# Breakout_v4.net
KiCad netlist of a schematic drawn in Altium Designer
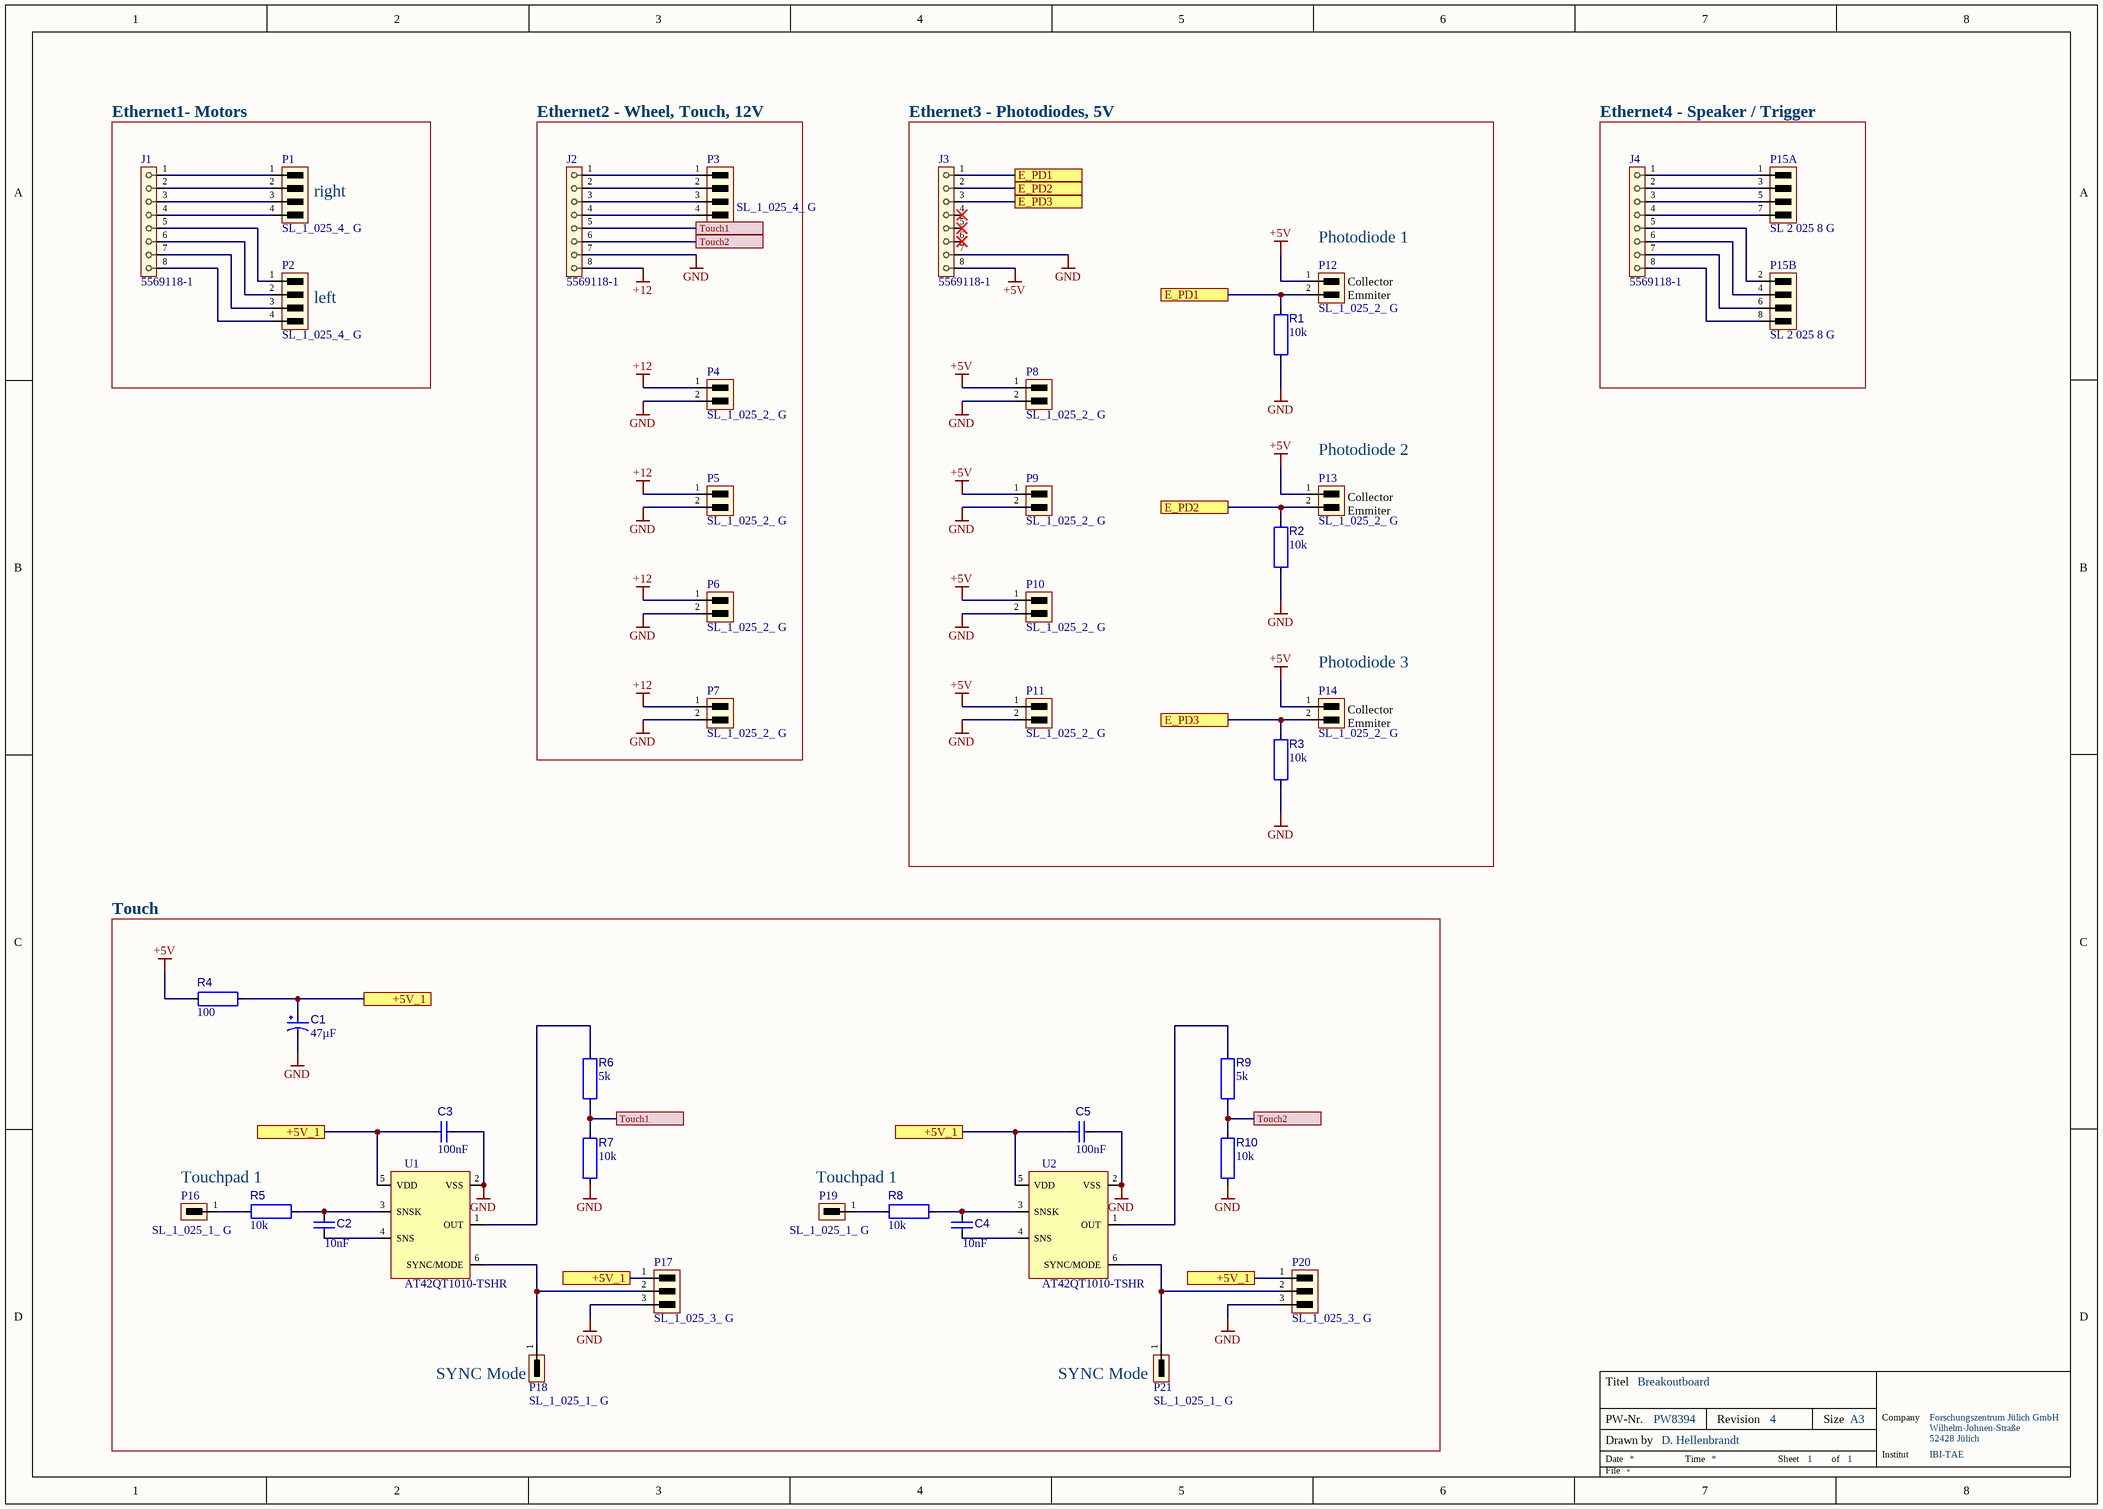
[diagram p0: Breakout_v4.SchDoc]

(export (version "E")
  (design (tool "Eeschema 10.0.6"))
  (components
    (comp (ref "C1")
      (value "47µF")
      (footprint "WCAP-HTAH_D8H11.5")
      (description "Cap, 47Uf, 50V, Alu Elec, Hybrid, Rad Rohs Compliant: Yes")
      (fields
        (field (name "MANUFACTURER") "Würth Elektronik")
        (field (name "TOLERANCE") "20%")
        (field (name "USER") "IBI-TAE")
      )
      (libsource (lib "Forschungszentrum Jülich GmbH") (part "CAP-P-2"))
    )
    (comp (ref "C2")
      (value "10nF")
      (footprint "Copy of 0805")
      (description "Kondensator 10nF 0805 X7R 50V 5%")
      (fields (field (name "Comment") "10nF 0805 X7R 50V 5%") (field (name "USER") "IBI-TAE"))
      (libsource (lib "Forschungszentrum Jülich GmbH") (part "CAP-NP-2"))
    )
    (comp (ref "C3")
      (value "100nF")
      (footprint "0805")
      (description "Kondensator 100nF 0805 X7R 100V 5%")
      (fields
        (field (name "TOLERANCE") "5%")
        (field (name "Comment") "100nF 0805 X7R 100V")
        (field (name "USER") "IBI-TAE")
      )
      (libsource (lib "Forschungszentrum Jülich GmbH") (part "CAP-NP-2"))
    )
    (comp (ref "C4")
      (value "10nF")
      (footprint "Copy of 0805")
      (description "Kondensator 10nF 0805 X7R 50V 5%")
      (fields (field (name "Comment") "10nF 0805 X7R 50V 5%") (field (name "USER") "IBI-TAE"))
      (libsource (lib "Forschungszentrum Jülich GmbH") (part "CAP-NP-2"))
    )
    (comp (ref "C5")
      (value "100nF")
      (footprint "0805")
      (description "Kondensator 100nF 0805 X7R 100V 5%")
      (fields
        (field (name "TOLERANCE") "5%")
        (field (name "Comment") "100nF 0805 X7R 100V")
        (field (name "USER") "IBI-TAE")
      )
      (libsource (lib "Forschungszentrum Jülich GmbH") (part "CAP-NP-2"))
    )
    (comp (ref "J1")
      (value "5569118-1")
      (footprint "5569118-1-Footprint-1")
      (description "Telecom and Datacom Connector, 8 Contact(s), Female, Right Angle, Solder Terminal, Locking, Jack")
      (fields (field (name "USER") "IBI-TAE"))
      (libsource (lib "Forschungszentrum Jülich GmbH") (part "5569118-1"))
    )
    (comp (ref "J2")
      (value "5569118-1")
      (footprint "5569118-1-Footprint-1")
      (description "Telecom and Datacom Connector, 8 Contact(s), Female, Right Angle, Solder Terminal, Locking, Jack")
      (fields (field (name "USER") "IBI-TAE"))
      (libsource (lib "Forschungszentrum Jülich GmbH") (part "5569118-1"))
    )
    (comp (ref "J3")
      (value "5569118-1")
      (footprint "5569118-1-Footprint-1")
      (description "Telecom and Datacom Connector, 8 Contact(s), Female, Right Angle, Solder Terminal, Locking, Jack")
      (fields (field (name "USER") "IBI-TAE"))
      (libsource (lib "Forschungszentrum Jülich GmbH") (part "5569118-1"))
    )
    (comp (ref "J4")
      (value "5569118-1")
      (footprint "5569118-1-Footprint-1")
      (description "Telecom and Datacom Connector, 8 Contact(s), Female, Right Angle, Solder Terminal, Locking, Jack")
      (fields (field (name "USER") "IBI-TAE"))
      (libsource (lib "Forschungszentrum Jülich GmbH") (part "5569118-1"))
    )
    (comp (ref "P1")
      (value "SL_1_025_4_ G")
      (footprint "SL_1_025_4_ G")
      (description "Fischer SL_1_025_4_ G, Stiftleiste, 1 Reiheb, 4 Pole, vergoldet")
      (fields (field (name "USER") "IBI-TAE"))
      (libsource (lib "Forschungszentrum Jülich GmbH") (part "SL_1_025_4_ G"))
    )
    (comp (ref "P2")
      (value "SL_1_025_4_ G")
      (footprint "SL_1_025_4_ G")
      (description "Fischer SL_1_025_4_ G, Stiftleiste, 1 Reiheb, 4 Pole, vergoldet")
      (fields (field (name "USER") "IBI-TAE"))
      (libsource (lib "Forschungszentrum Jülich GmbH") (part "SL_1_025_4_ G"))
    )
    (comp (ref "P3")
      (value "SL_1_025_4_ G")
      (footprint "SL_1_025_4_ G")
      (description "Fischer SL_1_025_4_ G, Stiftleiste, 1 Reiheb, 4 Pole, vergoldet")
      (fields (field (name "USER") "IBI-TAE"))
      (libsource (lib "Forschungszentrum Jülich GmbH") (part "SL_1_025_4_ G"))
    )
    (comp (ref "P4")
      (value "SL_1_025_2_ G")
      (footprint "SL_1_025_2_ G")
      (description "Fischer SL_1_025_2_ G, Stiftleiste, 1 Reiheb, 2 Pole, vergoldet")
      (fields (field (name "USER") "IBI-TAE"))
      (libsource (lib "Forschungszentrum Jülich GmbH") (part "SL_1_025_2_ G"))
    )
    (comp (ref "P5")
      (value "SL_1_025_2_ G")
      (footprint "SL_1_025_2_ G")
      (description "Fischer SL_1_025_2_ G, Stiftleiste, 1 Reiheb, 2 Pole, vergoldet")
      (fields (field (name "USER") "IBI-TAE"))
      (libsource (lib "Forschungszentrum Jülich GmbH") (part "SL_1_025_2_ G"))
    )
    (comp (ref "P6")
      (value "SL_1_025_2_ G")
      (footprint "SL_1_025_2_ G")
      (description "Fischer SL_1_025_2_ G, Stiftleiste, 1 Reiheb, 2 Pole, vergoldet")
      (fields (field (name "USER") "IBI-TAE"))
      (libsource (lib "Forschungszentrum Jülich GmbH") (part "SL_1_025_2_ G"))
    )
    (comp (ref "P7")
      (value "SL_1_025_2_ G")
      (footprint "SL_1_025_2_ G")
      (description "Fischer SL_1_025_2_ G, Stiftleiste, 1 Reiheb, 2 Pole, vergoldet")
      (fields (field (name "USER") "IBI-TAE"))
      (libsource (lib "Forschungszentrum Jülich GmbH") (part "SL_1_025_2_ G"))
    )
    (comp (ref "P8")
      (value "SL_1_025_2_ G")
      (footprint "SL_1_025_2_ G")
      (description "Fischer SL_1_025_2_ G, Stiftleiste, 1 Reiheb, 2 Pole, vergoldet")
      (fields (field (name "USER") "IBI-TAE"))
      (libsource (lib "Forschungszentrum Jülich GmbH") (part "SL_1_025_2_ G"))
    )
    (comp (ref "P9")
      (value "SL_1_025_2_ G")
      (footprint "SL_1_025_2_ G")
      (description "Fischer SL_1_025_2_ G, Stiftleiste, 1 Reiheb, 2 Pole, vergoldet")
      (fields (field (name "USER") "IBI-TAE"))
      (libsource (lib "Forschungszentrum Jülich GmbH") (part "SL_1_025_2_ G"))
    )
    (comp (ref "P10")
      (value "SL_1_025_2_ G")
      (footprint "SL_1_025_2_ G")
      (description "Fischer SL_1_025_2_ G, Stiftleiste, 1 Reiheb, 2 Pole, vergoldet")
      (fields (field (name "USER") "IBI-TAE"))
      (libsource (lib "Forschungszentrum Jülich GmbH") (part "SL_1_025_2_ G"))
    )
    (comp (ref "P11")
      (value "SL_1_025_2_ G")
      (footprint "SL_1_025_2_ G")
      (description "Fischer SL_1_025_2_ G, Stiftleiste, 1 Reiheb, 2 Pole, vergoldet")
      (fields (field (name "USER") "IBI-TAE"))
      (libsource (lib "Forschungszentrum Jülich GmbH") (part "SL_1_025_2_ G"))
    )
    (comp (ref "P12")
      (value "SL_1_025_2_ G")
      (footprint "SL_1_025_2_ G")
      (description "Fischer SL_1_025_2_ G, Stiftleiste, 1 Reiheb, 2 Pole, vergoldet")
      (fields (field (name "USER") "IBI-TAE"))
      (libsource (lib "Forschungszentrum Jülich GmbH") (part "SL_1_025_2_ G"))
    )
    (comp (ref "P13")
      (value "SL_1_025_2_ G")
      (footprint "SL_1_025_2_ G")
      (description "Fischer SL_1_025_2_ G, Stiftleiste, 1 Reiheb, 2 Pole, vergoldet")
      (fields (field (name "USER") "IBI-TAE"))
      (libsource (lib "Forschungszentrum Jülich GmbH") (part "SL_1_025_2_ G"))
    )
    (comp (ref "P14")
      (value "SL_1_025_2_ G")
      (footprint "SL_1_025_2_ G")
      (description "Fischer SL_1_025_2_ G, Stiftleiste, 1 Reiheb, 2 Pole, vergoldet")
      (fields (field (name "USER") "IBI-TAE"))
      (libsource (lib "Forschungszentrum Jülich GmbH") (part "SL_1_025_2_ G"))
    )
    (comp (ref "P15")
      (value "SL 2 025 8 G")
      (footprint "SL 2 025 2 G-Footprint-1")
      (description "Fischer  SL 2 025 8 G, Stiftleiste, 2 Reiheb, 8 Pole, vergoldet")
      (fields (field (name "USER") "IBI-TAE"))
      (libsource (lib "") (part "SL 2 025 8 G_1"))
    )
    (comp (ref "P16")
      (value "SL_1_025_1_ G")
      (footprint "Copy of SL_1_025_2_ G")
      (description "Fischer SL_1_025_1_ G, Stiftleiste, 1 Reiheb, 1 Pole, vergoldet")
      (fields (field (name "USER") "IBI-TAE"))
      (libsource (lib "") (part "SL_1_025_1_ G_1"))
    )
    (comp (ref "P17")
      (value "SL_1_025_3_ G")
      (footprint "Copy of SL_1_025_4_ G")
      (description "Fischer SL_1_025_3_ G, Stiftleiste, 1 Reiheb, 3 Pole, vergoldet")
      (fields (field (name "USER") "IBI-TAE"))
      (libsource (lib "Forschungszentrum Jülich GmbH") (part "SL_1_025_3_ G"))
    )
    (comp (ref "P18")
      (value "SL_1_025_1_ G")
      (footprint "Copy of SL_1_025_2_ G")
      (description "Fischer SL_1_025_1_ G, Stiftleiste, 1 Reiheb, 1 Pole, vergoldet")
      (fields (field (name "USER") "IBI-TAE"))
      (libsource (lib "Forschungszentrum Jülich GmbH") (part "SL_1_025_1_ G"))
    )
    (comp (ref "P19")
      (value "SL_1_025_1_ G")
      (footprint "Copy of SL_1_025_2_ G")
      (description "Fischer SL_1_025_1_ G, Stiftleiste, 1 Reiheb, 1 Pole, vergoldet")
      (fields (field (name "USER") "IBI-TAE"))
      (libsource (lib "") (part "SL_1_025_1_ G_1"))
    )
    (comp (ref "P20")
      (value "SL_1_025_3_ G")
      (footprint "Copy of SL_1_025_4_ G")
      (description "Fischer SL_1_025_3_ G, Stiftleiste, 1 Reiheb, 3 Pole, vergoldet")
      (fields (field (name "USER") "IBI-TAE"))
      (libsource (lib "Forschungszentrum Jülich GmbH") (part "SL_1_025_3_ G"))
    )
    (comp (ref "P21")
      (value "SL_1_025_1_ G")
      (footprint "Copy of SL_1_025_2_ G")
      (description "Fischer SL_1_025_1_ G, Stiftleiste, 1 Reiheb, 1 Pole, vergoldet")
      (fields (field (name "USER") "IBI-TAE"))
      (libsource (lib "Forschungszentrum Jülich GmbH") (part "SL_1_025_1_ G"))
    )
    (comp (ref "R1")
      (value "10k")
      (footprint "0805 (2012)")
      (description "Widerstand 10K 0805 200V 0,25W 0,5% 50ppm/K")
      (fields
        (field (name "POWER") "250mW")
        (field (name "TOLERANCE") "0.5%")
        (field (name "USER") "IBI-TAE")
      )
      (libsource (lib "Forschungszentrum Jülich GmbH") (part "RES-2"))
    )
    (comp (ref "R2")
      (value "10k")
      (footprint "0805 (2012)")
      (description "Widerstand 10K 0805 200V 0,25W 0,5% 50ppm/K")
      (fields
        (field (name "POWER") "250mW")
        (field (name "TOLERANCE") "0.5%")
        (field (name "USER") "IBI-TAE")
      )
      (libsource (lib "Forschungszentrum Jülich GmbH") (part "RES-2"))
    )
    (comp (ref "R3")
      (value "10k")
      (footprint "0805 (2012)")
      (description "Widerstand 10K 0805 200V 0,25W 0,5% 50ppm/K")
      (fields
        (field (name "POWER") "250mW")
        (field (name "TOLERANCE") "0.5%")
        (field (name "USER") "IBI-TAE")
      )
      (libsource (lib "Forschungszentrum Jülich GmbH") (part "RES-2"))
    )
    (comp (ref "R4")
      (value "100")
      (footprint "1206 (3216)")
      (description "Widerstans SMD 100R 1206 200V 0,25W 25ppm/K")
      (fields (field (name "POWER") "250mW") (field (name "TOLERANCE") "1%") (field (name "USER") "IBI-TAE"))
      (libsource (lib "Forschungszentrum Jülich GmbH") (part "RES-2"))
    )
    (comp (ref "R5")
      (value "10k")
      (footprint "0805 (2012)")
      (description "Widerstand 10K 0805 200V 0,25W 0,5% 50ppm/K")
      (fields
        (field (name "POWER") "250mW")
        (field (name "TOLERANCE") "0.5%")
        (field (name "USER") "IBI-TAE")
      )
      (libsource (lib "Forschungszentrum Jülich GmbH") (part "RES-2"))
    )
    (comp (ref "R6")
      (value "5k")
      (footprint "0805 (2012)")
      (description "Widerstand 5K 0805 100V 0,2W 25ppm/K")
      (fields
        (field (name "POWER") "200mW")
        (field (name "TOLERANCE") "0.1%")
        (field (name "USER") "IBI-TAE")
      )
      (libsource (lib "Forschungszentrum Jülich GmbH") (part "RES-2"))
    )
    (comp (ref "R7")
      (value "10k")
      (footprint "0805 (2012)")
      (description "Widerstand 10K 0805 200V 0,25W 0,5% 50ppm/K")
      (fields
        (field (name "POWER") "250mW")
        (field (name "TOLERANCE") "0.5%")
        (field (name "USER") "IBI-TAE")
      )
      (libsource (lib "Forschungszentrum Jülich GmbH") (part "RES-2"))
    )
    (comp (ref "R8")
      (value "10k")
      (footprint "0805 (2012)")
      (description "Widerstand 10K 0805 200V 0,25W 0,5% 50ppm/K")
      (fields
        (field (name "POWER") "250mW")
        (field (name "TOLERANCE") "0.5%")
        (field (name "USER") "IBI-TAE")
      )
      (libsource (lib "Forschungszentrum Jülich GmbH") (part "RES-2"))
    )
    (comp (ref "R9")
      (value "5k")
      (footprint "0805 (2012)")
      (description "Widerstand 5K 0805 100V 0,2W 25ppm/K")
      (fields
        (field (name "POWER") "200mW")
        (field (name "TOLERANCE") "0.1%")
        (field (name "USER") "IBI-TAE")
      )
      (libsource (lib "Forschungszentrum Jülich GmbH") (part "RES-2"))
    )
    (comp (ref "R10")
      (value "10k")
      (footprint "0805 (2012)")
      (description "Widerstand 10K 0805 200V 0,25W 0,5% 50ppm/K")
      (fields
        (field (name "POWER") "250mW")
        (field (name "TOLERANCE") "0.5%")
        (field (name "USER") "IBI-TAE")
      )
      (libsource (lib "Forschungszentrum Jülich GmbH") (part "RES-2"))
    )
    (comp (ref "U1")
      (value "AT42QT1010-TSHR")
      (footprint "6ST1_M")
      (description "Analog Circuit, 1 Func, PDSO6 ; Touchsensor; digital burst mode charge-transfer sensor ;")
      (fields (field (name "USER") "IBI-TAE"))
      (libsource (lib "Forschungszentrum Jülich GmbH") (part "IN-TSC-AT42QT1010-6"))
    )
    (comp (ref "U2")
      (value "AT42QT1010-TSHR")
      (footprint "6ST1_M")
      (description "Analog Circuit, 1 Func, PDSO6 ; Touchsensor; digital burst mode charge-transfer sensor ;")
      (fields (field (name "USER") "IBI-TAE"))
      (libsource (lib "Forschungszentrum Jülich GmbH") (part "IN-TSC-AT42QT1010-6"))
    )
  )
  (nets
    (net (code "1") (name "+5V") (class "Default")
      (node (ref "J3") (pin "8") (pinfunction "8_8") (pintype "passive"))
      (node (ref "P10") (pin "1") (pinfunction "1_1") (pintype "passive"))
      (node (ref "P11") (pin "1") (pinfunction "1_1") (pintype "passive"))
      (node (ref "P12") (pin "1") (pinfunction "1_1") (pintype "passive"))
      (node (ref "P13") (pin "1") (pinfunction "1_1") (pintype "passive"))
      (node (ref "P14") (pin "1") (pinfunction "1_1") (pintype "passive"))
      (node (ref "P8") (pin "1") (pinfunction "1_1") (pintype "passive"))
      (node (ref "P9") (pin "1") (pinfunction "1_1") (pintype "passive"))
      (node (ref "R4") (pin "2") (pinfunction "2_2") (pintype "passive"))
    )
    (net (code "2") (name "+12") (class "Default")
      (node (ref "J2") (pin "8") (pinfunction "8_8") (pintype "passive"))
      (node (ref "P4") (pin "1") (pinfunction "1_1") (pintype "passive"))
      (node (ref "P5") (pin "1") (pinfunction "1_1") (pintype "passive"))
      (node (ref "P6") (pin "1") (pinfunction "1_1") (pintype "passive"))
      (node (ref "P7") (pin "1") (pinfunction "1_1") (pintype "passive"))
    )
    (net (code "3") (name "/+5V_1") (class "Default")
      (node (ref "C1") (pin "1") (pinfunction "1_1") (pintype "passive"))
      (node (ref "C3") (pin "1") (pinfunction "1_1") (pintype "passive"))
      (node (ref "C5") (pin "1") (pinfunction "1_1") (pintype "passive"))
      (node (ref "P17") (pin "1") (pinfunction "1_1") (pintype "passive"))
      (node (ref "P20") (pin "1") (pinfunction "1_1") (pintype "passive"))
      (node (ref "R4") (pin "1") (pinfunction "1_1") (pintype "passive"))
      (node (ref "U1") (pin "5") (pinfunction "VDD_5") (pintype "power_in"))
      (node (ref "U2") (pin "5") (pinfunction "VDD_5") (pintype "power_in"))
    )
    (net (code "4") (name "/E_PD1") (class "Default")
      (node (ref "J3") (pin "1") (pinfunction "1_1") (pintype "passive"))
      (node (ref "P12") (pin "2") (pinfunction "2_2") (pintype "passive"))
      (node (ref "R1") (pin "2") (pinfunction "2_2") (pintype "passive"))
    )
    (net (code "5") (name "/E_PD2") (class "Default")
      (node (ref "J3") (pin "2") (pinfunction "2_2") (pintype "passive"))
      (node (ref "P13") (pin "2") (pinfunction "2_2") (pintype "passive"))
      (node (ref "R2") (pin "2") (pinfunction "2_2") (pintype "passive"))
    )
    (net (code "6") (name "/E_PD3") (class "Default")
      (node (ref "J3") (pin "3") (pinfunction "3_3") (pintype "passive"))
      (node (ref "P14") (pin "2") (pinfunction "2_2") (pintype "passive"))
      (node (ref "R3") (pin "2") (pinfunction "2_2") (pintype "passive"))
    )
    (net (code "7") (name "/Touch1") (class "Default")
      (node (ref "J2") (pin "5") (pinfunction "5_5") (pintype "passive"))
      (node (ref "R6") (pin "1") (pinfunction "1_1") (pintype "passive"))
      (node (ref "R7") (pin "2") (pinfunction "2_2") (pintype "passive"))
    )
    (net (code "8") (name "/Touch2") (class "Default")
      (node (ref "J2") (pin "6") (pinfunction "6_6") (pintype "passive"))
      (node (ref "R10") (pin "2") (pinfunction "2_2") (pintype "passive"))
      (node (ref "R9") (pin "1") (pinfunction "1_1") (pintype "passive"))
    )
    (net (code "9") (name "GND") (class "Default")
      (node (ref "C1") (pin "2") (pinfunction "2_2") (pintype "passive"))
      (node (ref "C3") (pin "2") (pinfunction "2_2") (pintype "passive"))
      (node (ref "C5") (pin "2") (pinfunction "2_2") (pintype "passive"))
      (node (ref "J2") (pin "7") (pinfunction "7_7") (pintype "passive"))
      (node (ref "J3") (pin "7") (pinfunction "7_7") (pintype "passive"))
      (node (ref "P10") (pin "2") (pinfunction "2_2") (pintype "passive"))
      (node (ref "P11") (pin "2") (pinfunction "2_2") (pintype "passive"))
      (node (ref "P17") (pin "3") (pinfunction "3_3") (pintype "passive"))
      (node (ref "P20") (pin "3") (pinfunction "3_3") (pintype "passive"))
      (node (ref "P4") (pin "2") (pinfunction "2_2") (pintype "passive"))
      (node (ref "P5") (pin "2") (pinfunction "2_2") (pintype "passive"))
      (node (ref "P6") (pin "2") (pinfunction "2_2") (pintype "passive"))
      (node (ref "P7") (pin "2") (pinfunction "2_2") (pintype "passive"))
      (node (ref "P8") (pin "2") (pinfunction "2_2") (pintype "passive"))
      (node (ref "P9") (pin "2") (pinfunction "2_2") (pintype "passive"))
      (node (ref "R1") (pin "1") (pinfunction "1_1") (pintype "passive"))
      (node (ref "R10") (pin "1") (pinfunction "1_1") (pintype "passive"))
      (node (ref "R2") (pin "1") (pinfunction "1_1") (pintype "passive"))
      (node (ref "R3") (pin "1") (pinfunction "1_1") (pintype "passive"))
      (node (ref "R7") (pin "1") (pinfunction "1_1") (pintype "passive"))
      (node (ref "U1") (pin "2") (pinfunction "VSS_2") (pintype "power_in"))
      (node (ref "U2") (pin "2") (pinfunction "VSS_2") (pintype "power_in"))
    )
    (net (code "10") (name "Net-(J1-Pad1)") (class "Default")
      (node (ref "J1") (pin "1") (pinfunction "1_1") (pintype "passive"))
      (node (ref "P1") (pin "1") (pinfunction "1_1") (pintype "passive"))
    )
    (net (code "11") (name "Net-(J1-Pad2)") (class "Default")
      (node (ref "J1") (pin "2") (pinfunction "2_2") (pintype "passive"))
      (node (ref "P1") (pin "2") (pinfunction "2_2") (pintype "passive"))
    )
    (net (code "12") (name "Net-(J1-Pad3)") (class "Default")
      (node (ref "J1") (pin "3") (pinfunction "3_3") (pintype "passive"))
      (node (ref "P1") (pin "3") (pinfunction "3_3") (pintype "passive"))
    )
    (net (code "13") (name "Net-(J1-Pad4)") (class "Default")
      (node (ref "J1") (pin "4") (pinfunction "4_4") (pintype "passive"))
      (node (ref "P1") (pin "4") (pinfunction "4_4") (pintype "passive"))
    )
    (net (code "14") (name "Net-(J1-Pad5)") (class "Default")
      (node (ref "J1") (pin "5") (pinfunction "5_5") (pintype "passive"))
      (node (ref "P2") (pin "1") (pinfunction "1_1") (pintype "passive"))
    )
    (net (code "15") (name "Net-(J1-Pad6)") (class "Default")
      (node (ref "J1") (pin "6") (pinfunction "6_6") (pintype "passive"))
      (node (ref "P2") (pin "2") (pinfunction "2_2") (pintype "passive"))
    )
    (net (code "16") (name "Net-(J1-Pad7)") (class "Default")
      (node (ref "J1") (pin "7") (pinfunction "7_7") (pintype "passive"))
      (node (ref "P2") (pin "3") (pinfunction "3_3") (pintype "passive"))
    )
    (net (code "17") (name "Net-(J1-Pad8)") (class "Default")
      (node (ref "J1") (pin "8") (pinfunction "8_8") (pintype "passive"))
      (node (ref "P2") (pin "4") (pinfunction "4_4") (pintype "passive"))
    )
    (net (code "18") (name "Net-(J2-Pad1)") (class "Default")
      (node (ref "J2") (pin "1") (pinfunction "1_1") (pintype "passive"))
      (node (ref "P3") (pin "1") (pinfunction "1_1") (pintype "passive"))
    )
    (net (code "19") (name "Net-(J2-Pad2)") (class "Default")
      (node (ref "J2") (pin "2") (pinfunction "2_2") (pintype "passive"))
      (node (ref "P3") (pin "2") (pinfunction "2_2") (pintype "passive"))
    )
    (net (code "20") (name "Net-(J2-Pad3)") (class "Default")
      (node (ref "J2") (pin "3") (pinfunction "3_3") (pintype "passive"))
      (node (ref "P3") (pin "3") (pinfunction "3_3") (pintype "passive"))
    )
    (net (code "21") (name "Net-(J2-Pad4)") (class "Default")
      (node (ref "J2") (pin "4") (pinfunction "4_4") (pintype "passive"))
      (node (ref "P3") (pin "4") (pinfunction "4_4") (pintype "passive"))
    )
    (net (code "22") (name "Net-(J4-Pad1)") (class "Default")
      (node (ref "J4") (pin "1") (pinfunction "1_1") (pintype "passive"))
      (node (ref "P15") (pin "1") (pinfunction "1_1") (pintype "passive"))
    )
    (net (code "23") (name "Net-(J4-Pad2)") (class "Default")
      (node (ref "J4") (pin "2") (pinfunction "2_2") (pintype "passive"))
      (node (ref "P15") (pin "3") (pinfunction "3_3") (pintype "passive"))
    )
    (net (code "24") (name "Net-(J4-Pad3)") (class "Default")
      (node (ref "J4") (pin "3") (pinfunction "3_3") (pintype "passive"))
      (node (ref "P15") (pin "5") (pinfunction "5_5") (pintype "passive"))
    )
    (net (code "25") (name "Net-(J4-Pad4)") (class "Default")
      (node (ref "J4") (pin "4") (pinfunction "4_4") (pintype "passive"))
      (node (ref "P15") (pin "7") (pinfunction "7_7") (pintype "passive"))
    )
    (net (code "26") (name "Net-(J4-Pad5)") (class "Default")
      (node (ref "J4") (pin "5") (pinfunction "5_5") (pintype "passive"))
      (node (ref "P15") (pin "2") (pinfunction "2_2") (pintype "passive"))
    )
    (net (code "27") (name "Net-(J4-Pad6)") (class "Default")
      (node (ref "J4") (pin "6") (pinfunction "6_6") (pintype "passive"))
      (node (ref "P15") (pin "4") (pinfunction "4_4") (pintype "passive"))
    )
    (net (code "28") (name "Net-(J4-Pad7)") (class "Default")
      (node (ref "J4") (pin "7") (pinfunction "7_7") (pintype "passive"))
      (node (ref "P15") (pin "6") (pinfunction "6_6") (pintype "passive"))
    )
    (net (code "29") (name "Net-(J4-Pad8)") (class "Default")
      (node (ref "J4") (pin "8") (pinfunction "8_8") (pintype "passive"))
      (node (ref "P15") (pin "8") (pinfunction "8_8") (pintype "passive"))
    )
    (net (code "30") (name "Net-(P16-Pad1)") (class "Default")
      (node (ref "P16") (pin "1") (pinfunction "1_1") (pintype "passive"))
      (node (ref "R5") (pin "1") (pinfunction "1_1") (pintype "passive"))
    )
    (net (code "31") (name "Net-(P19-Pad1)") (class "Default")
      (node (ref "P19") (pin "1") (pinfunction "1_1") (pintype "passive"))
      (node (ref "R8") (pin "1") (pinfunction "1_1") (pintype "passive"))
    )
    (net (code "32") (name "Net-(U1-OUT)") (class "Default")
      (node (ref "R6") (pin "2") (pinfunction "2_2") (pintype "passive"))
      (node (ref "U1") (pin "1") (pinfunction "OUT_1") (pintype "passive"))
    )
    (net (code "33") (name "Net-(U1-SNS)") (class "Default")
      (node (ref "C2") (pin "1") (pinfunction "1_1") (pintype "passive"))
      (node (ref "U1") (pin "4") (pinfunction "SNS_4") (pintype "passive"))
    )
    (net (code "34") (name "Net-(U1-SNSK)") (class "Default")
      (node (ref "C2") (pin "2") (pinfunction "2_2") (pintype "passive"))
      (node (ref "R5") (pin "2") (pinfunction "2_2") (pintype "passive"))
      (node (ref "U1") (pin "3") (pinfunction "SNSK_3") (pintype "passive"))
    )
    (net (code "35") (name "Net-(U1-SYNC{slash}MODE)") (class "Default")
      (node (ref "P17") (pin "2") (pinfunction "2_2") (pintype "passive"))
      (node (ref "P18") (pin "1") (pinfunction "1_1") (pintype "passive"))
      (node (ref "U1") (pin "6") (pinfunction "SYNC/MODE_6") (pintype "passive"))
    )
    (net (code "36") (name "Net-(U2-OUT)") (class "Default")
      (node (ref "R9") (pin "2") (pinfunction "2_2") (pintype "passive"))
      (node (ref "U2") (pin "1") (pinfunction "OUT_1") (pintype "passive"))
    )
    (net (code "37") (name "Net-(U2-SNS)") (class "Default")
      (node (ref "C4") (pin "1") (pinfunction "1_1") (pintype "passive"))
      (node (ref "U2") (pin "4") (pinfunction "SNS_4") (pintype "passive"))
    )
    (net (code "38") (name "Net-(U2-SNSK)") (class "Default")
      (node (ref "C4") (pin "2") (pinfunction "2_2") (pintype "passive"))
      (node (ref "R8") (pin "2") (pinfunction "2_2") (pintype "passive"))
      (node (ref "U2") (pin "3") (pinfunction "SNSK_3") (pintype "passive"))
    )
    (net (code "39") (name "Net-(U2-SYNC{slash}MODE)") (class "Default")
      (node (ref "P20") (pin "2") (pinfunction "2_2") (pintype "passive"))
      (node (ref "P21") (pin "1") (pinfunction "1_1") (pintype "passive"))
      (node (ref "U2") (pin "6") (pinfunction "SYNC/MODE_6") (pintype "passive"))
    )
    (net (code "40") (name "unconnected-(J3-Pad4)") (class "Default")
      (node (ref "J3") (pin "4") (pinfunction "4_4") (pintype "passive+no_connect"))
    )
    (net (code "41") (name "unconnected-(J3-Pad5)") (class "Default")
      (node (ref "J3") (pin "5") (pinfunction "5_5") (pintype "passive+no_connect"))
    )
    (net (code "42") (name "unconnected-(J3-Pad6)") (class "Default")
      (node (ref "J3") (pin "6") (pinfunction "6_6") (pintype "passive+no_connect"))
    )
  )
)
